# powerSupply.net
KiCad netlist of a schematic drawn in EAGLE
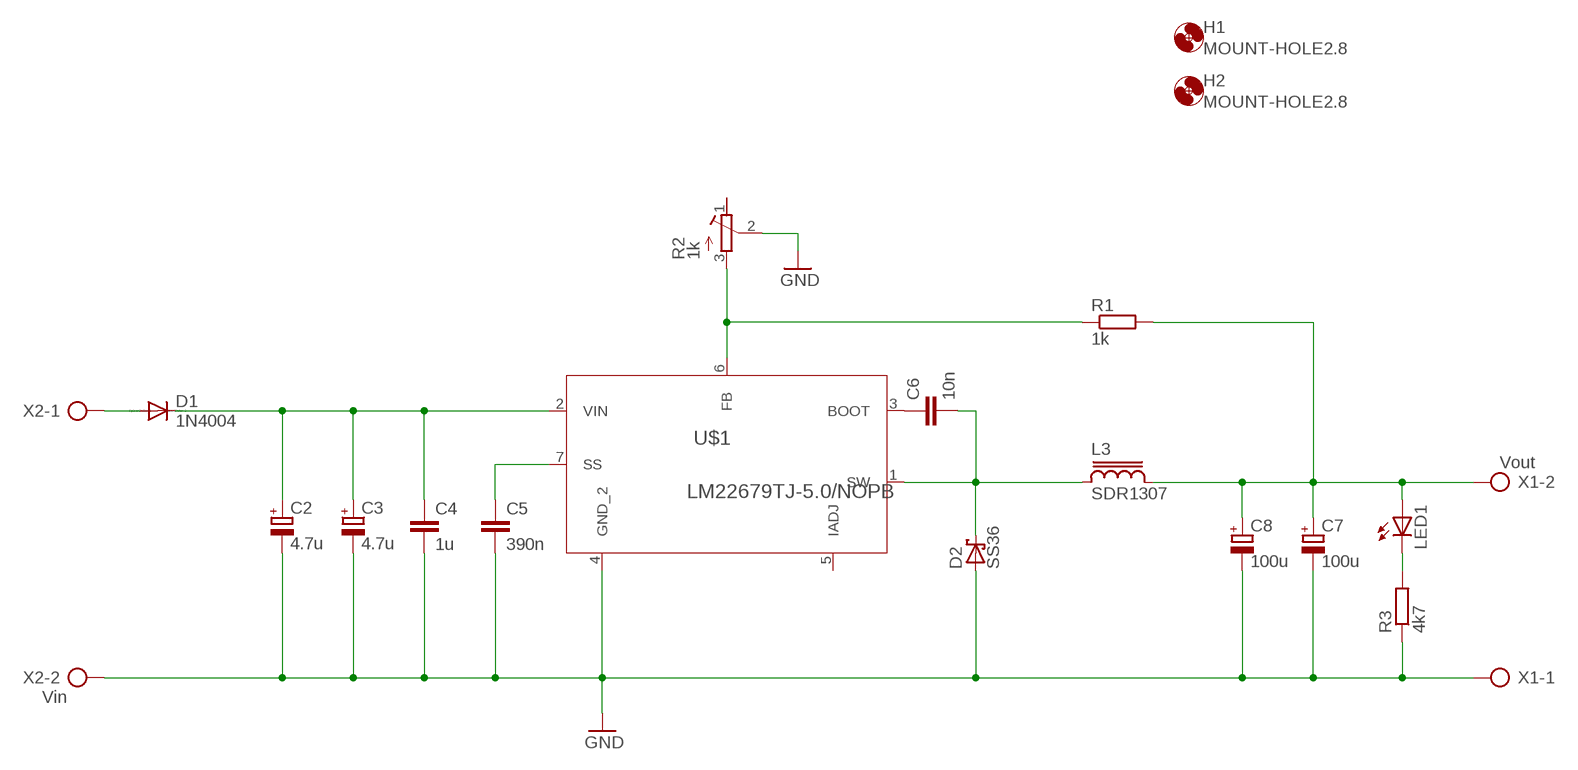
[diagram p0: schematic, sheet 1]

(export (version "E")
  (design (tool "Eeschema 10.0.6"))
  (components
    (comp (ref "C2")
      (value "4.7u")
      (footprint "eagle-import:E2,5-5")
      (libsource (lib "eagle-import") (part "CPOL-EUE2.5-5"))
    )
    (comp (ref "C3")
      (value "4.7u")
      (footprint "eagle-import:E2,5-5")
      (libsource (lib "eagle-import") (part "CPOL-EUE2.5-5"))
    )
    (comp (ref "C4")
      (value "1u")
      (footprint "eagle-import:C1206")
      (libsource (lib "eagle-import") (part "C-EUC1206"))
    )
    (comp (ref "C5")
      (value "390n")
      (footprint "eagle-import:C0603")
      (libsource (lib "eagle-import") (part "C-EUC0603"))
    )
    (comp (ref "C6")
      (value "10n")
      (footprint "eagle-import:C0805")
      (libsource (lib "eagle-import") (part "C-EUC0805"))
    )
    (comp (ref "C7")
      (value "100u")
      (footprint "eagle-import:PANASONIC_D")
      (libsource (lib "eagle-import") (part "CPOL-EUD"))
    )
    (comp (ref "C8")
      (value "100u")
      (footprint "eagle-import:PANASONIC_D")
      (libsource (lib "eagle-import") (part "CPOL-EUD"))
    )
    (comp (ref "D1")
      (value "1N4004")
      (footprint "eagle-import:DO41-10")
      (libsource (lib "eagle-import") (part "1N4004"))
    )
    (comp (ref "D2")
      (value "SS36")
      (footprint "eagle-import:SMC")
      (libsource (lib "eagle-import") (part "SCHOTTKY-DIODESMC"))
    )
    (comp (ref "H1")
      (value "MOUNT-HOLE2.8")
      (footprint "eagle-import:2,8")
      (libsource (lib "eagle-import") (part "MOUNT-HOLE2.8"))
    )
    (comp (ref "H2")
      (value "MOUNT-HOLE2.8")
      (footprint "eagle-import:2,8")
      (libsource (lib "eagle-import") (part "MOUNT-HOLE2.8"))
    )
    (comp (ref "L3")
      (value "SDR1307")
      (footprint "eagle-import:SDR1307")
      (libsource (lib "eagle-import") (part "SDR1307"))
    )
    (comp (ref "LED1")
      (value "LEDCHIPLED_1206")
      (footprint "eagle-import:CHIPLED_1206")
      (libsource (lib "eagle-import") (part "LEDCHIPLED_1206"))
    )
    (comp (ref "R1")
      (value "1k")
      (footprint "eagle-import:R1206")
      (libsource (lib "eagle-import") (part "R-EU_R1206"))
    )
    (comp (ref "R2")
      (value "1k")
      (footprint "eagle-import:RTRIM3314J")
      (libsource (lib "eagle-import") (part "R-TRIMM3314J"))
    )
    (comp (ref "R3")
      (value "4k7")
      (footprint "eagle-import:R1206")
      (libsource (lib "eagle-import") (part "R-EU_R1206"))
    )
    (comp (ref "U$1")
      (value "LM22679TJ-5.0/NOPB")
      (footprint "eagle-import:TJ7A")
      (libsource (lib "eagle-import") (part "LM22679TJ-5.0/NOPB"))
    )
    (comp (ref "X1")
      (value "Vout")
      (footprint "eagle-import:AK500_2")
      (libsource (lib "eagle-import") (part "AK500/2"))
    )
    (comp (ref "X2")
      (value "Vin")
      (footprint "eagle-import:AK500_2")
      (libsource (lib "eagle-import") (part "AK500/2"))
    )
  )
  (nets
    (net (code "1") (name "GND") (class "Default")
      (node (ref "C2") (pin "-") (pinfunction "-_-") (pintype "passive"))
      (node (ref "C3") (pin "-") (pinfunction "-_-") (pintype "passive"))
      (node (ref "C4") (pin "2") (pinfunction "2_2") (pintype "passive"))
      (node (ref "C5") (pin "2") (pinfunction "2_2") (pintype "passive"))
      (node (ref "C7") (pin "-") (pinfunction "-_-") (pintype "passive"))
      (node (ref "C8") (pin "-") (pinfunction "-_-") (pintype "passive"))
      (node (ref "D2") (pin "A") (pinfunction "A_A") (pintype "passive"))
      (node (ref "R2") (pin "2") (pinfunction "S_2") (pintype "passive"))
      (node (ref "R3") (pin "1") (pinfunction "1_1") (pintype "passive"))
      (node (ref "U$1") (pin "4") (pinfunction "GND_2_4") (pintype "passive"))
      (node (ref "X1") (pin "1") (pinfunction "KL_1") (pintype "passive"))
      (node (ref "X2") (pin "2") (pinfunction "KL_2") (pintype "passive"))
    )
    (net (code "2") (name "Net-(LED1-PadC)") (class "Default")
      (node (ref "LED1") (pin "C") (pinfunction "C_C") (pintype "passive"))
      (node (ref "R3") (pin "2") (pinfunction "2_2") (pintype "passive"))
    )
    (net (code "3") (name "Net-(R2-A)") (class "Default")
      (node (ref "R1") (pin "1") (pinfunction "1_1") (pintype "passive"))
      (node (ref "R2") (pin "3") (pinfunction "A_3") (pintype "passive"))
      (node (ref "U$1") (pin "6") (pinfunction "FB_6") (pintype "passive"))
    )
    (net (code "4") (name "Net-(U$1-BOOT)") (class "Default")
      (node (ref "C6") (pin "1") (pinfunction "1_1") (pintype "passive"))
      (node (ref "U$1") (pin "3") (pinfunction "BOOT_3") (pintype "passive"))
    )
    (net (code "5") (name "Net-(U$1-SS)") (class "Default")
      (node (ref "C5") (pin "1") (pinfunction "1_1") (pintype "passive"))
      (node (ref "U$1") (pin "7") (pinfunction "SS_7") (pintype "passive"))
    )
    (net (code "6") (name "Net-(U$1-SW)") (class "Default")
      (node (ref "C6") (pin "2") (pinfunction "2_2") (pintype "passive"))
      (node (ref "D2") (pin "C") (pinfunction "C_C") (pintype "passive"))
      (node (ref "L3") (pin "1") (pinfunction "1_1") (pintype "passive"))
      (node (ref "U$1") (pin "1") (pinfunction "SW_1") (pintype "passive"))
    )
    (net (code "7") (name "Net-(U$1-VIN)") (class "Default")
      (node (ref "C2") (pin "+") (pinfunction "+_+") (pintype "passive"))
      (node (ref "C3") (pin "+") (pinfunction "+_+") (pintype "passive"))
      (node (ref "C4") (pin "1") (pinfunction "1_1") (pintype "passive"))
      (node (ref "D1") (pin "C") (pinfunction "C_C") (pintype "passive"))
      (node (ref "U$1") (pin "2") (pinfunction "VIN_2") (pintype "passive"))
    )
    (net (code "8") (name "Net-(X1B-KL)") (class "Default")
      (node (ref "C7") (pin "+") (pinfunction "+_+") (pintype "passive"))
      (node (ref "C8") (pin "+") (pinfunction "+_+") (pintype "passive"))
      (node (ref "L3") (pin "2") (pinfunction "2_2") (pintype "passive"))
      (node (ref "LED1") (pin "A") (pinfunction "A_A") (pintype "passive"))
      (node (ref "R1") (pin "2") (pinfunction "2_2") (pintype "passive"))
      (node (ref "X1") (pin "2") (pinfunction "KL_2") (pintype "passive"))
    )
    (net (code "9") (name "Net-(X2A-KL)") (class "Default")
      (node (ref "D1") (pin "A") (pinfunction "A_A") (pintype "passive"))
      (node (ref "X2") (pin "1") (pinfunction "KL_1") (pintype "passive"))
    )
    (net (code "10") (name "unconnected-(R2-E-Pad1)") (class "Default")
      (node (ref "R2") (pin "1") (pinfunction "E_1") (pintype "passive"))
    )
    (net (code "11") (name "unconnected-(U$1-IADJ-Pad5)") (class "Default")
      (node (ref "U$1") (pin "5") (pinfunction "IADJ_5") (pintype "passive"))
    )
  )
)
